# schema_dubbellayer.net
KiCad netlist of a schematic drawn in EAGLE
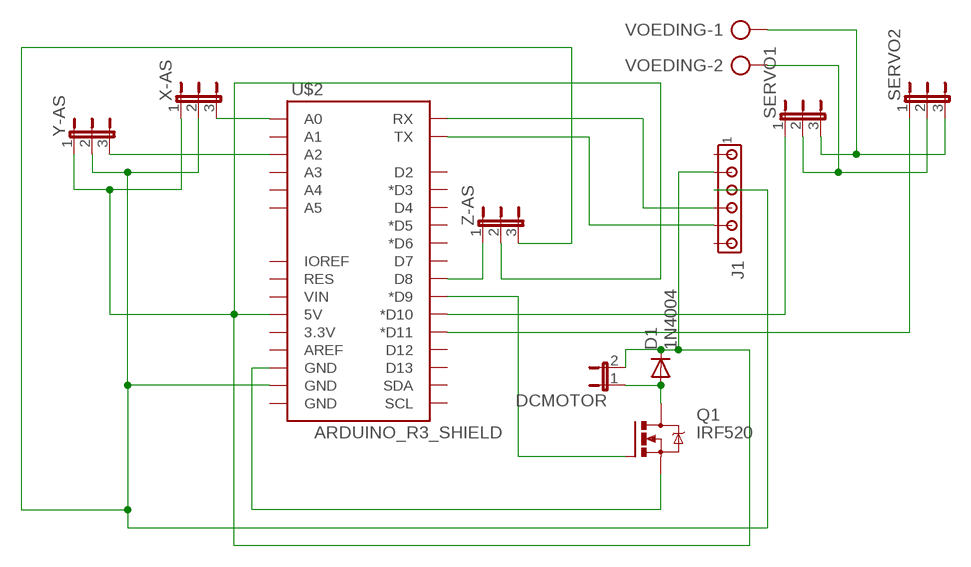
[diagram p0: schematic, sheet 1]

(export (version "E")
  (design (tool "Eeschema 10.0.6"))
  (components
    (comp (ref "D1")
      (value "1N4004")
      (footprint "eagle-import:DO41-10")
      (libsource (lib "eagle-import") (part "1N4004"))
    )
    (comp (ref "DCMOTOR")
      (value "JP1E")
      (footprint "eagle-import:JP1")
      (libsource (lib "eagle-import") (part "JP1E"))
    )
    (comp (ref "J1")
      (value "MTA06-100")
      (footprint "eagle-import:10X06MTA")
      (libsource (lib "eagle-import") (part "MTA06-100"))
    )
    (comp (ref "Q1")
      (value "IRF520")
      (footprint "eagle-import:TO220BV")
      (libsource (lib "eagle-import") (part "IRF520"))
    )
    (comp (ref "SERVO1")
      (value "JP2E")
      (footprint "eagle-import:JP2")
      (libsource (lib "eagle-import") (part "JP2E"))
    )
    (comp (ref "SERVO2")
      (value "JP2E")
      (footprint "eagle-import:JP2")
      (libsource (lib "eagle-import") (part "JP2E"))
    )
    (comp (ref "U$2")
      (value "ARDUINO_R3_SHIELD")
      (footprint "eagle-import:UNO_R3_SHIELD")
      (libsource (lib "eagle-import") (part "ARDUINO_R3_SHIELD"))
    )
    (comp (ref "VOEDING")
      (value "AK300/2")
      (footprint "eagle-import:AK300_2")
      (libsource (lib "eagle-import") (part "AK300/2"))
    )
    (comp (ref "X-AS")
      (value "JP2E")
      (footprint "eagle-import:JP2")
      (libsource (lib "eagle-import") (part "JP2E"))
    )
    (comp (ref "Y-AS")
      (value "JP2E")
      (footprint "eagle-import:JP2")
      (libsource (lib "eagle-import") (part "JP2E"))
    )
    (comp (ref "Z-AS")
      (value "JP2E")
      (footprint "eagle-import:JP2")
      (libsource (lib "eagle-import") (part "JP2E"))
    )
  )
  (nets
    (net (code "1") (name "Net-(D1-PadA)") (class "Default")
      (node (ref "D1") (pin "A") (pinfunction "A_A") (pintype "passive"))
      (node (ref "DCMOTOR") (pin "1") (pinfunction "1_1") (pintype "passive"))
      (node (ref "Q1") (pin "D") (pinfunction "D_D") (pintype "passive"))
    )
    (net (code "2") (name "Net-(J1-2)") (class "Default")
      (node (ref "D1") (pin "C") (pinfunction "C_C") (pintype "passive"))
      (node (ref "DCMOTOR") (pin "2") (pinfunction "2_2") (pintype "passive"))
      (node (ref "J1") (pin "5") (pinfunction "2_5") (pintype "passive"))
      (node (ref "U$2") (pin "5V") (pinfunction "5V_5V") (pintype "bidirectional"))
      (node (ref "X-AS") (pin "1") (pinfunction "1_1") (pintype "passive"))
      (node (ref "Y-AS") (pin "1") (pinfunction "1_1") (pintype "passive"))
      (node (ref "Z-AS") (pin "2") (pinfunction "2_2") (pintype "passive"))
    )
    (net (code "3") (name "Net-(J1-3)") (class "Default")
      (node (ref "J1") (pin "4") (pinfunction "3_4") (pintype "passive"))
      (node (ref "U$2") (pin "GND@1") (pinfunction "GND_GND@1") (pintype "bidirectional"))
      (node (ref "X-AS") (pin "2") (pinfunction "2_2") (pintype "passive"))
      (node (ref "Y-AS") (pin "2") (pinfunction "2_2") (pintype "passive"))
      (node (ref "Z-AS") (pin "3") (pinfunction "3_3") (pintype "passive"))
    )
    (net (code "4") (name "Net-(J1-4)") (class "Default")
      (node (ref "J1") (pin "3") (pinfunction "4_3") (pintype "passive"))
      (node (ref "U$2") (pin "RX") (pinfunction "RX_RX") (pintype "bidirectional"))
    )
    (net (code "5") (name "Net-(J1-5)") (class "Default")
      (node (ref "J1") (pin "2") (pinfunction "5_2") (pintype "passive"))
      (node (ref "U$2") (pin "TX") (pinfunction "TX_TX") (pintype "bidirectional"))
    )
    (net (code "6") (name "Net-(Q1-PadS)") (class "Default")
      (node (ref "Q1") (pin "S") (pinfunction "S_S") (pintype "passive"))
      (node (ref "U$2") (pin "GND@2") (pinfunction "GND_GND@2") (pintype "bidirectional"))
    )
    (net (code "7") (name "Net-(U$2-*D9)") (class "Default")
      (node (ref "Q1") (pin "G") (pinfunction "G_G") (pintype "passive"))
      (node (ref "U$2") (pin "D9") (pinfunction "*D9_D9") (pintype "bidirectional"))
    )
    (net (code "8") (name "Net-(U$2-*D10)") (class "Default")
      (node (ref "SERVO1") (pin "1") (pinfunction "1_1") (pintype "passive"))
      (node (ref "U$2") (pin "D10") (pinfunction "*D10_D10") (pintype "bidirectional"))
    )
    (net (code "9") (name "Net-(U$2-*D11)") (class "Default")
      (node (ref "SERVO2") (pin "1") (pinfunction "1_1") (pintype "passive"))
      (node (ref "U$2") (pin "D11") (pinfunction "*D11_D11") (pintype "bidirectional"))
    )
    (net (code "10") (name "Net-(U$2-PadA0)") (class "Default")
      (node (ref "U$2") (pin "A0") (pinfunction "A0_A0") (pintype "bidirectional"))
      (node (ref "X-AS") (pin "3") (pinfunction "3_3") (pintype "passive"))
    )
    (net (code "11") (name "Net-(U$2-PadA2)") (class "Default")
      (node (ref "U$2") (pin "A2") (pinfunction "A2_A2") (pintype "bidirectional"))
      (node (ref "Y-AS") (pin "3") (pinfunction "3_3") (pintype "passive"))
    )
    (net (code "12") (name "Net-(U$2-PadD8)") (class "Default")
      (node (ref "U$2") (pin "D8") (pinfunction "D8_D8") (pintype "bidirectional"))
      (node (ref "Z-AS") (pin "1") (pinfunction "1_1") (pintype "passive"))
    )
    (net (code "13") (name "Net-(VOEDINGA-KL)") (class "Default")
      (node (ref "SERVO1") (pin "3") (pinfunction "3_3") (pintype "passive"))
      (node (ref "SERVO2") (pin "3") (pinfunction "3_3") (pintype "passive"))
      (node (ref "VOEDING") (pin "1") (pinfunction "KL_1") (pintype "passive"))
    )
    (net (code "14") (name "Net-(VOEDINGB-KL)") (class "Default")
      (node (ref "SERVO1") (pin "2") (pinfunction "2_2") (pintype "passive"))
      (node (ref "SERVO2") (pin "2") (pinfunction "2_2") (pintype "passive"))
      (node (ref "VOEDING") (pin "2") (pinfunction "KL_2") (pintype "passive"))
    )
    (net (code "15") (name "unconnected-(J1-1-Pad6)") (class "Default")
      (node (ref "J1") (pin "6") (pinfunction "1_6") (pintype "passive"))
    )
    (net (code "16") (name "unconnected-(J1-6-Pad1)") (class "Default")
      (node (ref "J1") (pin "1") (pinfunction "6_1") (pintype "passive"))
    )
    (net (code "17") (name "unconnected-(U$2-*D3-PadD3)") (class "Default")
      (node (ref "U$2") (pin "D3") (pinfunction "*D3_D3") (pintype "bidirectional"))
    )
    (net (code "18") (name "unconnected-(U$2-*D5-PadD5)") (class "Default")
      (node (ref "U$2") (pin "D5") (pinfunction "*D5_D5") (pintype "bidirectional"))
    )
    (net (code "19") (name "unconnected-(U$2-*D6-PadD6)") (class "Default")
      (node (ref "U$2") (pin "D6") (pinfunction "*D6_D6") (pintype "bidirectional"))
    )
    (net (code "20") (name "unconnected-(U$2-GND-PadGND@0)") (class "Default")
      (node (ref "U$2") (pin "GND@0") (pinfunction "GND_GND@0") (pintype "bidirectional"))
    )
    (net (code "21") (name "unconnected-(U$2-Pad3.3V)") (class "Default")
      (node (ref "U$2") (pin "3.3V") (pinfunction "3.3V_3.3V") (pintype "bidirectional"))
    )
    (net (code "22") (name "unconnected-(U$2-PadA1)") (class "Default")
      (node (ref "U$2") (pin "A1") (pinfunction "A1_A1") (pintype "bidirectional"))
    )
    (net (code "23") (name "unconnected-(U$2-PadA3)") (class "Default")
      (node (ref "U$2") (pin "A3") (pinfunction "A3_A3") (pintype "bidirectional"))
    )
    (net (code "24") (name "unconnected-(U$2-PadA4)") (class "Default")
      (node (ref "U$2") (pin "A4") (pinfunction "A4_A4") (pintype "bidirectional"))
    )
    (net (code "25") (name "unconnected-(U$2-PadA5)") (class "Default")
      (node (ref "U$2") (pin "A5") (pinfunction "A5_A5") (pintype "bidirectional"))
    )
    (net (code "26") (name "unconnected-(U$2-PadAREF)") (class "Default")
      (node (ref "U$2") (pin "AREF") (pinfunction "AREF_AREF") (pintype "bidirectional"))
    )
    (net (code "27") (name "unconnected-(U$2-PadD2)") (class "Default")
      (node (ref "U$2") (pin "D2") (pinfunction "D2_D2") (pintype "bidirectional"))
    )
    (net (code "28") (name "unconnected-(U$2-PadD4)") (class "Default")
      (node (ref "U$2") (pin "D4") (pinfunction "D4_D4") (pintype "bidirectional"))
    )
    (net (code "29") (name "unconnected-(U$2-PadD7)") (class "Default")
      (node (ref "U$2") (pin "D7") (pinfunction "D7_D7") (pintype "bidirectional"))
    )
    (net (code "30") (name "unconnected-(U$2-PadD12)") (class "Default")
      (node (ref "U$2") (pin "D12") (pinfunction "D12_D12") (pintype "bidirectional"))
    )
    (net (code "31") (name "unconnected-(U$2-PadD13)") (class "Default")
      (node (ref "U$2") (pin "D13") (pinfunction "D13_D13") (pintype "bidirectional"))
    )
    (net (code "32") (name "unconnected-(U$2-PadIOREF)") (class "Default")
      (node (ref "U$2") (pin "IOREF") (pinfunction "IOREF_IOREF") (pintype "bidirectional"))
    )
    (net (code "33") (name "unconnected-(U$2-PadRES)") (class "Default")
      (node (ref "U$2") (pin "RES") (pinfunction "RES_RES") (pintype "bidirectional"))
    )
    (net (code "34") (name "unconnected-(U$2-PadSCL)") (class "Default")
      (node (ref "U$2") (pin "SCL") (pinfunction "SCL_SCL") (pintype "bidirectional"))
    )
    (net (code "35") (name "unconnected-(U$2-PadSDA)") (class "Default")
      (node (ref "U$2") (pin "SDA") (pinfunction "SDA_SDA") (pintype "bidirectional"))
    )
    (net (code "36") (name "unconnected-(U$2-PadVIN)") (class "Default")
      (node (ref "U$2") (pin "VIN") (pinfunction "VIN_VIN") (pintype "bidirectional"))
    )
  )
)
